# SCH_dddd_2025-12-29.net
KiCad netlist of a schematic drawn in EasyEDA
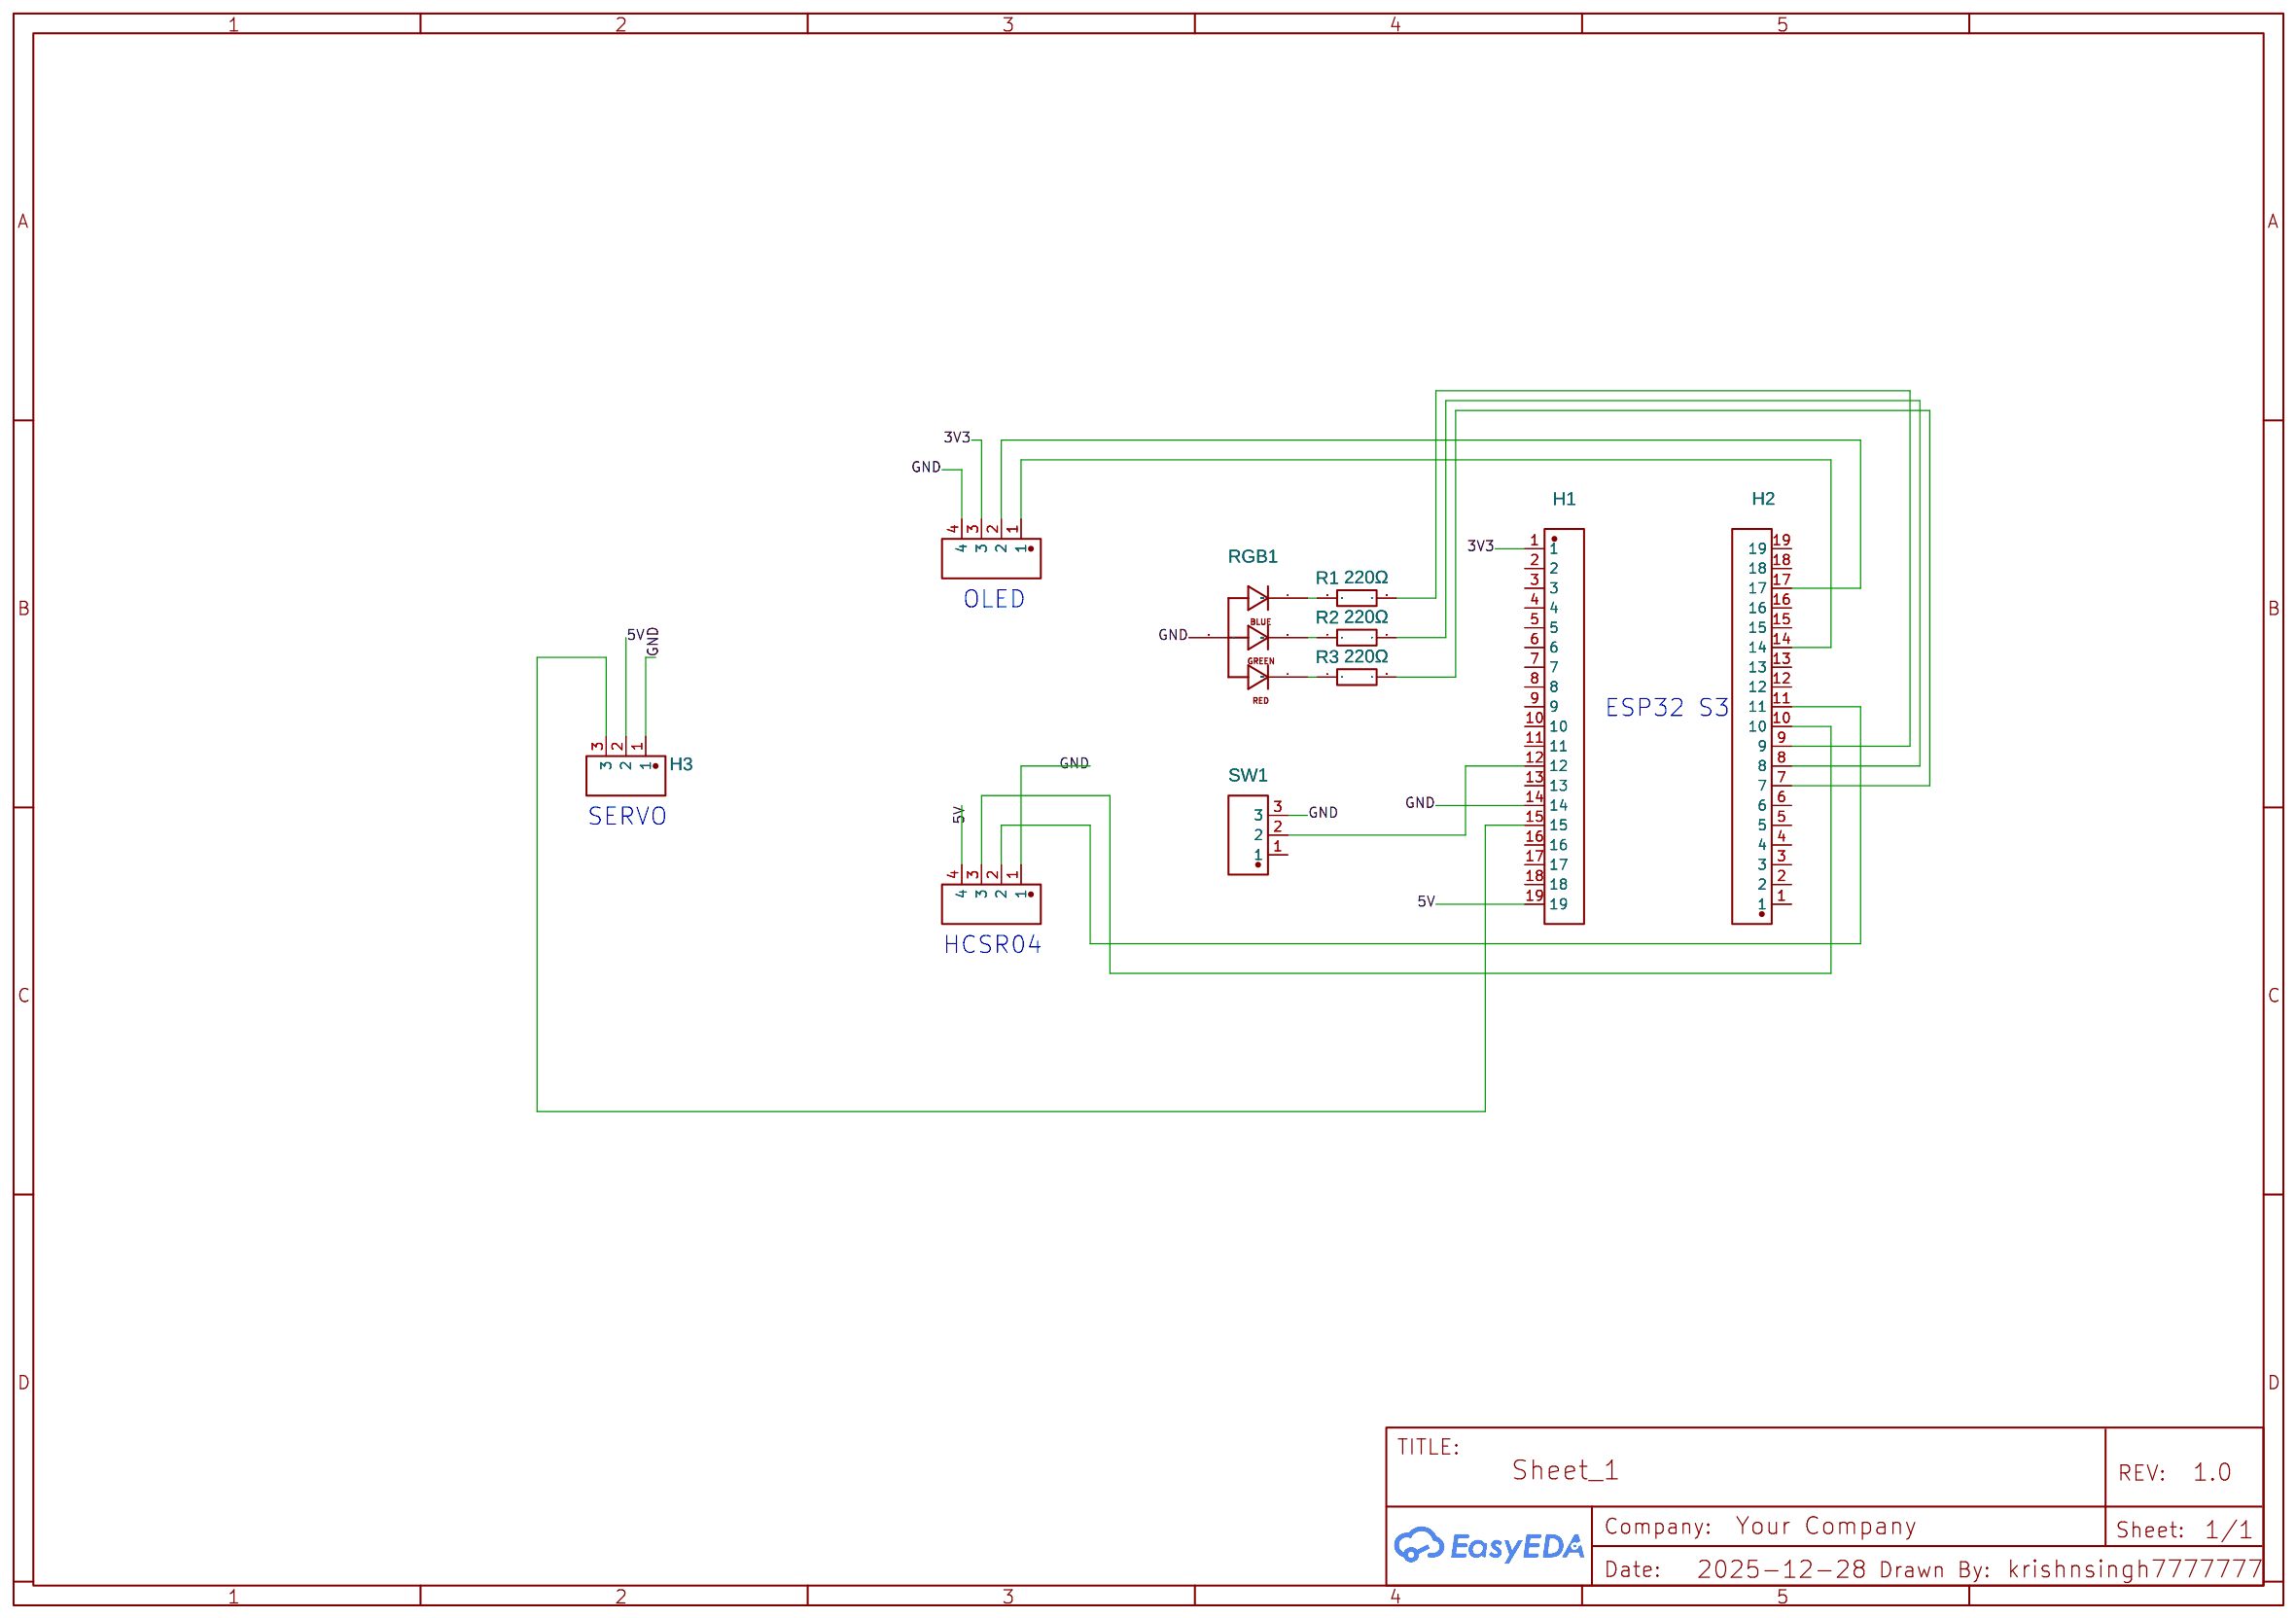
[diagram p0: schematic sheet]

(export (version "E")
  (design (tool "Eeschema 10.0.6"))
  (components
    (comp (ref "CN1")
      (value "OLED")
      (fields (field (name "Manufacturer Part") "Straight 4 pins magnetic connector Female"))
      (libsource (lib "") (part "STRAIGHT 4 PINS MAGNETIC CONNECTOR FEMALE"))
    )
    (comp (ref "CN2")
      (value "HCSR04")
      (fields (field (name "Manufacturer Part") "Straight 4 pins magnetic connector Female"))
      (libsource (lib "") (part "STRAIGHT 4 PINS MAGNETIC CONNECTOR FEMALE"))
    )
    (comp (ref "H1")
      (value "KH-2.54PH180-1X19P-L11.5")
      (fields (field (name "Manufacturer") "kinghelm(金航标)"))
      (libsource (lib "") (part "KH-2.54PH180-1X19P-L11.5"))
    )
    (comp (ref "H2")
      (value "KH-2.54PH180-1X19P-L11.5")
      (fields (field (name "Manufacturer") "kinghelm(金航标)"))
      (libsource (lib "") (part "KH-2.54PH180-1X19P-L11.5_1"))
    )
    (comp (ref "H3")
      (value "SRVO")
      (fields
        (field (name "Manufacturer Part") "HX PH254-01-03-Z-L11.5 pcb pin header")
        (field (name "Manufacturer") "hanxia(韩下)")
      )
      (libsource (lib "") (part "HX PH254-01-03-Z-L11.5 PCB PIN HEADER"))
    )
    (comp (ref "R1")
      (value "220Ω")
      (fields (field (name "Manufacturer Part") "AC0603FR-07220RL") (field (name "Manufacturer") "YAGEO(国巨)"))
      (libsource (lib "") (part "AC0603FR-07220RL"))
    )
    (comp (ref "R2")
      (value "220Ω")
      (fields (field (name "Manufacturer Part") "AC0603FR-07220RL") (field (name "Manufacturer") "YAGEO(国巨)"))
      (libsource (lib "") (part "AC0603FR-07220RL"))
    )
    (comp (ref "R3")
      (value "220Ω")
      (fields (field (name "Manufacturer Part") "AC0603FR-07220RL") (field (name "Manufacturer") "YAGEO(国巨)"))
      (libsource (lib "") (part "AC0603FR-07220RL"))
    )
    (comp (ref "RGB1") (value "RGB") (libsource (lib "") (part "LED-RGB-CA-THRUDIFFUSE")))
    (comp (ref "SW1")
      (value "SW1")
      (fields
        (field (name "Manufacturer Part") "SS-12D10L10")
        (field (name "Manufacturer") "XKB Connection(中国星坤)")
      )
      (libsource (lib "") (part "SS-12D10L10"))
    )
  )
  (nets
    (net (code "1") (name "/3V3") (class "Default")
      (node (ref "CN1") (pin "3") (pinfunction "3_3") (pintype "unspecified"))
      (node (ref "H1") (pin "1") (pinfunction "1_1") (pintype "unspecified"))
    )
    (net (code "2") (name "/5V") (class "Default")
      (node (ref "CN2") (pin "4") (pinfunction "4_4") (pintype "unspecified"))
      (node (ref "H1") (pin "19") (pinfunction "19_19") (pintype "unspecified"))
      (node (ref "H3") (pin "2") (pinfunction "2_2") (pintype "unspecified"))
    )
    (net (code "3") (name "/GND") (class "Default")
      (node (ref "CN1") (pin "4") (pinfunction "4_4") (pintype "unspecified"))
      (node (ref "CN2") (pin "1") (pinfunction "1_1") (pintype "unspecified"))
      (node (ref "H1") (pin "14") (pinfunction "14_14") (pintype "unspecified"))
      (node (ref "H3") (pin "1") (pinfunction "1_1") (pintype "unspecified"))
      (node (ref "RGB1") (pin "2") (pinfunction "ANODE_2") (pintype "unspecified"))
      (node (ref "SW1") (pin "3") (pinfunction "3_3") (pintype "unspecified"))
    )
    (net (code "4") (name "Net-(CN1-Pad1)") (class "Default")
      (node (ref "CN1") (pin "1") (pinfunction "1_1") (pintype "unspecified"))
      (node (ref "H2") (pin "14") (pinfunction "14_14") (pintype "unspecified"))
    )
    (net (code "5") (name "Net-(CN1-Pad2)") (class "Default")
      (node (ref "CN1") (pin "2") (pinfunction "2_2") (pintype "unspecified"))
      (node (ref "H2") (pin "17") (pinfunction "17_17") (pintype "unspecified"))
    )
    (net (code "6") (name "Net-(CN2-Pad2)") (class "Default")
      (node (ref "CN2") (pin "2") (pinfunction "2_2") (pintype "unspecified"))
      (node (ref "H2") (pin "11") (pinfunction "11_11") (pintype "unspecified"))
    )
    (net (code "7") (name "Net-(CN2-Pad3)") (class "Default")
      (node (ref "CN2") (pin "3") (pinfunction "3_3") (pintype "unspecified"))
      (node (ref "H2") (pin "10") (pinfunction "10_10") (pintype "unspecified"))
    )
    (net (code "8") (name "Net-(H1-Pad12)") (class "Default")
      (node (ref "H1") (pin "12") (pinfunction "12_12") (pintype "unspecified"))
      (node (ref "SW1") (pin "2") (pinfunction "2_2") (pintype "unspecified"))
    )
    (net (code "9") (name "Net-(H1-Pad15)") (class "Default")
      (node (ref "H1") (pin "15") (pinfunction "15_15") (pintype "unspecified"))
      (node (ref "H3") (pin "3") (pinfunction "3_3") (pintype "unspecified"))
    )
    (net (code "10") (name "Net-(H2-Pad7)") (class "Default")
      (node (ref "H2") (pin "7") (pinfunction "7_7") (pintype "unspecified"))
      (node (ref "R3") (pin "2") (pinfunction "2_2") (pintype "input"))
    )
    (net (code "11") (name "Net-(H2-Pad8)") (class "Default")
      (node (ref "H2") (pin "8") (pinfunction "8_8") (pintype "unspecified"))
      (node (ref "R2") (pin "2") (pinfunction "2_2") (pintype "input"))
    )
    (net (code "12") (name "Net-(H2-Pad9)") (class "Default")
      (node (ref "H2") (pin "9") (pinfunction "9_9") (pintype "unspecified"))
      (node (ref "R1") (pin "2") (pinfunction "2_2") (pintype "input"))
    )
    (net (code "13") (name "Net-(RGB1-BLUE_CATHODE)") (class "Default")
      (node (ref "R1") (pin "1") (pinfunction "1_1") (pintype "input"))
      (node (ref "RGB1") (pin "4") (pinfunction "BLUE_CATHODE_4") (pintype "unspecified"))
    )
    (net (code "14") (name "Net-(RGB1-GREEN_CATHODE)") (class "Default")
      (node (ref "R2") (pin "1") (pinfunction "1_1") (pintype "input"))
      (node (ref "RGB1") (pin "3") (pinfunction "GREEN_CATHODE_3") (pintype "unspecified"))
    )
    (net (code "15") (name "Net-(RGB1-RED_CATHODE)") (class "Default")
      (node (ref "R3") (pin "1") (pinfunction "1_1") (pintype "input"))
      (node (ref "RGB1") (pin "1") (pinfunction "RED_CATHODE_1") (pintype "unspecified"))
    )
    (net (code "16") (name "unconnected-(H1-Pad2)") (class "Default")
      (node (ref "H1") (pin "2") (pinfunction "2_2") (pintype "unspecified"))
    )
    (net (code "17") (name "unconnected-(H1-Pad3)") (class "Default")
      (node (ref "H1") (pin "3") (pinfunction "3_3") (pintype "unspecified"))
    )
    (net (code "18") (name "unconnected-(H1-Pad4)") (class "Default")
      (node (ref "H1") (pin "4") (pinfunction "4_4") (pintype "unspecified"))
    )
    (net (code "19") (name "unconnected-(H1-Pad5)") (class "Default")
      (node (ref "H1") (pin "5") (pinfunction "5_5") (pintype "unspecified"))
    )
    (net (code "20") (name "unconnected-(H1-Pad6)") (class "Default")
      (node (ref "H1") (pin "6") (pinfunction "6_6") (pintype "unspecified"))
    )
    (net (code "21") (name "unconnected-(H1-Pad7)") (class "Default")
      (node (ref "H1") (pin "7") (pinfunction "7_7") (pintype "unspecified"))
    )
    (net (code "22") (name "unconnected-(H1-Pad8)") (class "Default")
      (node (ref "H1") (pin "8") (pinfunction "8_8") (pintype "unspecified"))
    )
    (net (code "23") (name "unconnected-(H1-Pad9)") (class "Default")
      (node (ref "H1") (pin "9") (pinfunction "9_9") (pintype "unspecified"))
    )
    (net (code "24") (name "unconnected-(H1-Pad10)") (class "Default")
      (node (ref "H1") (pin "10") (pinfunction "10_10") (pintype "unspecified"))
    )
    (net (code "25") (name "unconnected-(H1-Pad11)") (class "Default")
      (node (ref "H1") (pin "11") (pinfunction "11_11") (pintype "unspecified"))
    )
    (net (code "26") (name "unconnected-(H1-Pad13)") (class "Default")
      (node (ref "H1") (pin "13") (pinfunction "13_13") (pintype "unspecified"))
    )
    (net (code "27") (name "unconnected-(H1-Pad16)") (class "Default")
      (node (ref "H1") (pin "16") (pinfunction "16_16") (pintype "unspecified"))
    )
    (net (code "28") (name "unconnected-(H1-Pad17)") (class "Default")
      (node (ref "H1") (pin "17") (pinfunction "17_17") (pintype "unspecified"))
    )
    (net (code "29") (name "unconnected-(H1-Pad18)") (class "Default")
      (node (ref "H1") (pin "18") (pinfunction "18_18") (pintype "unspecified"))
    )
    (net (code "30") (name "unconnected-(H2-Pad1)") (class "Default")
      (node (ref "H2") (pin "1") (pinfunction "1_1") (pintype "unspecified"))
    )
    (net (code "31") (name "unconnected-(H2-Pad2)") (class "Default")
      (node (ref "H2") (pin "2") (pinfunction "2_2") (pintype "unspecified"))
    )
    (net (code "32") (name "unconnected-(H2-Pad3)") (class "Default")
      (node (ref "H2") (pin "3") (pinfunction "3_3") (pintype "unspecified"))
    )
    (net (code "33") (name "unconnected-(H2-Pad4)") (class "Default")
      (node (ref "H2") (pin "4") (pinfunction "4_4") (pintype "unspecified"))
    )
    (net (code "34") (name "unconnected-(H2-Pad5)") (class "Default")
      (node (ref "H2") (pin "5") (pinfunction "5_5") (pintype "unspecified"))
    )
    (net (code "35") (name "unconnected-(H2-Pad6)") (class "Default")
      (node (ref "H2") (pin "6") (pinfunction "6_6") (pintype "unspecified"))
    )
    (net (code "36") (name "unconnected-(H2-Pad12)") (class "Default")
      (node (ref "H2") (pin "12") (pinfunction "12_12") (pintype "unspecified"))
    )
    (net (code "37") (name "unconnected-(H2-Pad13)") (class "Default")
      (node (ref "H2") (pin "13") (pinfunction "13_13") (pintype "unspecified"))
    )
    (net (code "38") (name "unconnected-(H2-Pad15)") (class "Default")
      (node (ref "H2") (pin "15") (pinfunction "15_15") (pintype "unspecified"))
    )
    (net (code "39") (name "unconnected-(H2-Pad16)") (class "Default")
      (node (ref "H2") (pin "16") (pinfunction "16_16") (pintype "unspecified"))
    )
    (net (code "40") (name "unconnected-(H2-Pad18)") (class "Default")
      (node (ref "H2") (pin "18") (pinfunction "18_18") (pintype "unspecified"))
    )
    (net (code "41") (name "unconnected-(H2-Pad19)") (class "Default")
      (node (ref "H2") (pin "19") (pinfunction "19_19") (pintype "unspecified"))
    )
    (net (code "42") (name "unconnected-(SW1-Pad1)") (class "Default")
      (node (ref "SW1") (pin "1") (pinfunction "1_1") (pintype "unspecified"))
    )
  )
)
